# usb2serial-pic14f1454.net
KiCad netlist of a schematic drawn in EAGLE
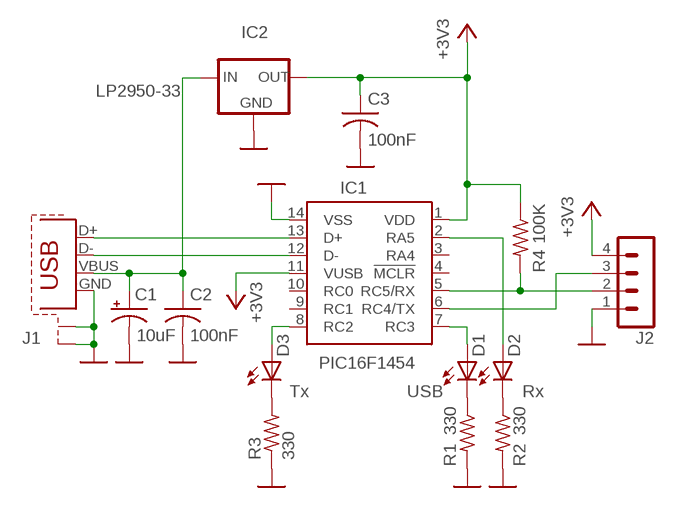
[diagram p0: schematic, sheet 1]

(export (version "E")
  (design (tool "Eeschema 10.0.6"))
  (components
    (comp (ref "C1")
      (value "10uF")
      (footprint "eagle-import:E2-4")
      (libsource (lib "eagle-import") (part "CPOL-USE2-4"))
    )
    (comp (ref "C2")
      (value "100nF")
      (footprint "eagle-import:C050-025X075")
      (libsource (lib "eagle-import") (part "C-US050-025X075"))
    )
    (comp (ref "C3")
      (value "100nF")
      (footprint "eagle-import:C050-025X075")
      (libsource (lib "eagle-import") (part "C-US050-025X075"))
    )
    (comp (ref "D1")
      (value "LED5MM")
      (footprint "eagle-import:LED5MM")
      (libsource (lib "eagle-import") (part "LED5MM"))
    )
    (comp (ref "D2")
      (value "LED5MM")
      (footprint "eagle-import:LED5MM")
      (libsource (lib "eagle-import") (part "LED5MM"))
    )
    (comp (ref "D3")
      (value "LED5MM")
      (footprint "eagle-import:LED5MM")
      (libsource (lib "eagle-import") (part "LED5MM"))
    )
    (comp (ref "IC1")
      (value "PIC16F1454")
      (footprint "eagle-import:DIL14")
      (libsource (lib "eagle-import") (part "PIC16F1454"))
    )
    (comp (ref "IC2")
      (value "LP2950-33")
      (footprint "eagle-import:78LXX")
      (libsource (lib "eagle-import") (part "78LXX"))
    )
    (comp (ref "J1")
      (value "USB-SHIELD-A-H")
      (footprint "eagle-import:USB-A-H")
      (libsource (lib "eagle-import") (part "USB-SHIELD-A-H"))
    )
    (comp (ref "J2")
      (value "J2")
      (footprint "eagle-import:MA04-1")
      (libsource (lib "eagle-import") (part "MA04-1"))
    )
    (comp (ref "R1")
      (value "330")
      (footprint "eagle-import:0207_10")
      (libsource (lib "eagle-import") (part "R-US_0207/10"))
    )
    (comp (ref "R2")
      (value "330")
      (footprint "eagle-import:0207_10")
      (libsource (lib "eagle-import") (part "R-US_0207/10"))
    )
    (comp (ref "R3")
      (value "330")
      (footprint "eagle-import:0207_10")
      (libsource (lib "eagle-import") (part "R-US_0207/10"))
    )
    (comp (ref "R4")
      (value "100K")
      (footprint "eagle-import:0207_10")
      (libsource (lib "eagle-import") (part "R-US_0207/10"))
    )
  )
  (nets
    (net (code "1") (name "+3V3") (class "Default")
      (node (ref "C3") (pin "1") (pinfunction "1_1") (pintype "passive"))
      (node (ref "IC1") (pin "1") (pinfunction "VDD_1") (pintype "power_in"))
      (node (ref "IC1") (pin "11") (pinfunction "VUSB_11") (pintype "power_in"))
      (node (ref "IC2") (pin "OUT") (pinfunction "OUT_OUT") (pintype "passive"))
      (node (ref "J2") (pin "4") (pinfunction "4_4") (pintype "passive"))
      (node (ref "R4") (pin "1") (pinfunction "1_1") (pintype "passive"))
    )
    (net (code "2") (name "GND") (class "Default")
      (node (ref "C1") (pin "-") (pinfunction "-_-") (pintype "passive"))
      (node (ref "C2") (pin "2") (pinfunction "2_2") (pintype "passive"))
      (node (ref "C3") (pin "2") (pinfunction "2_2") (pintype "passive"))
      (node (ref "IC1") (pin "14") (pinfunction "VSS_14") (pintype "power_in"))
      (node (ref "IC2") (pin "GND") (pinfunction "GND_GND") (pintype "input"))
      (node (ref "J1") (pin "GND") (pinfunction "GND_GND") (pintype "passive"))
      (node (ref "J1") (pin "GND2") (pinfunction "S1_GND2") (pintype "passive"))
      (node (ref "J1") (pin "GND3") (pinfunction "S2_GND3") (pintype "passive"))
      (node (ref "J2") (pin "1") (pinfunction "1_1") (pintype "passive"))
      (node (ref "R1") (pin "2") (pinfunction "2_2") (pintype "passive"))
      (node (ref "R2") (pin "2") (pinfunction "2_2") (pintype "passive"))
      (node (ref "R3") (pin "1") (pinfunction "1_1") (pintype "passive"))
    )
    (net (code "3") (name "Net-(C1-Pad+)") (class "Default")
      (node (ref "C1") (pin "+") (pinfunction "+_+") (pintype "passive"))
      (node (ref "C2") (pin "1") (pinfunction "1_1") (pintype "passive"))
      (node (ref "IC2") (pin "IN") (pinfunction "IN_IN") (pintype "input"))
      (node (ref "J1") (pin "VBUS") (pinfunction "VBUS_VBUS") (pintype "passive"))
    )
    (net (code "4") (name "Net-(D1-C)") (class "Default")
      (node (ref "D1") (pin "K") (pinfunction "C_K") (pintype "passive"))
      (node (ref "R1") (pin "1") (pinfunction "1_1") (pintype "passive"))
    )
    (net (code "5") (name "Net-(D2-C)") (class "Default")
      (node (ref "D2") (pin "K") (pinfunction "C_K") (pintype "passive"))
      (node (ref "R2") (pin "1") (pinfunction "1_1") (pintype "passive"))
    )
    (net (code "6") (name "Net-(D3-C)") (class "Default")
      (node (ref "D3") (pin "K") (pinfunction "C_K") (pintype "passive"))
      (node (ref "R3") (pin "2") (pinfunction "2_2") (pintype "passive"))
    )
    (net (code "7") (name "Net-(IC1-D+)") (class "Default")
      (node (ref "IC1") (pin "13") (pinfunction "D+_13") (pintype "passive"))
      (node (ref "J1") (pin "D+") (pinfunction "D+_D+") (pintype "passive"))
    )
    (net (code "8") (name "Net-(IC1-D-)") (class "Default")
      (node (ref "IC1") (pin "12") (pinfunction "D-_12") (pintype "passive"))
      (node (ref "J1") (pin "D-") (pinfunction "D-_D-") (pintype "passive"))
    )
    (net (code "9") (name "Net-(IC1-RA5)") (class "Default")
      (node (ref "D2") (pin "A") (pinfunction "A_A") (pintype "passive"))
      (node (ref "IC1") (pin "2") (pinfunction "RA5_2") (pintype "bidirectional"))
    )
    (net (code "10") (name "Net-(IC1-RC2)") (class "Default")
      (node (ref "D3") (pin "A") (pinfunction "A_A") (pintype "passive"))
      (node (ref "IC1") (pin "8") (pinfunction "RC2_8") (pintype "bidirectional"))
    )
    (net (code "11") (name "Net-(IC1-RC3)") (class "Default")
      (node (ref "D1") (pin "A") (pinfunction "A_A") (pintype "passive"))
      (node (ref "IC1") (pin "7") (pinfunction "RC3_7") (pintype "bidirectional"))
    )
    (net (code "12") (name "Net-(IC1-RC4{slash}TX)") (class "Default")
      (node (ref "IC1") (pin "6") (pinfunction "RC4/TX_6") (pintype "input"))
      (node (ref "J2") (pin "3") (pinfunction "3_3") (pintype "passive"))
    )
    (net (code "13") (name "Net-(IC1-RC5{slash}RX)") (class "Default")
      (node (ref "IC1") (pin "5") (pinfunction "RC5/RX_5") (pintype "bidirectional"))
      (node (ref "J2") (pin "2") (pinfunction "2_2") (pintype "passive"))
      (node (ref "R4") (pin "2") (pinfunction "2_2") (pintype "passive"))
    )
    (net (code "14") (name "unconnected-(IC1-RA4-Pad3)") (class "Default")
      (node (ref "IC1") (pin "3") (pinfunction "RA4_3") (pintype "bidirectional"))
    )
    (net (code "15") (name "unconnected-(IC1-RC0-Pad10)") (class "Default")
      (node (ref "IC1") (pin "10") (pinfunction "RC0_10") (pintype "bidirectional"))
    )
    (net (code "16") (name "unconnected-(IC1-RC1-Pad9)") (class "Default")
      (node (ref "IC1") (pin "9") (pinfunction "RC1_9") (pintype "bidirectional"))
    )
    (net (code "17") (name "unconnected-(IC1-~{MCLR}-Pad4)") (class "Default")
      (node (ref "IC1") (pin "4") (pinfunction "~{MCLR}_4") (pintype "bidirectional"))
    )
  )
)
